# VREG_RT9166-28PVL_with_EN.net
KiCad netlist of a schematic drawn in Altium Designer
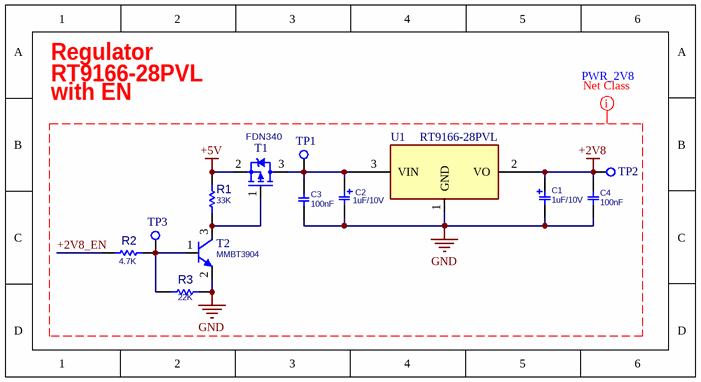
[diagram p0: VREG RT9166-28PVL with EN.SchDoc]

(export (version "E")
  (design (tool "Eeschema 10.0.6"))
  (components
    (comp (ref "C1")
      (value "1uF/10V")
      (footprint "C_TN_3216")
      (description "CAP, SMD, TAN")
      (libsource (lib "Passive") (part "CAP_SMD_TAN"))
    )
    (comp (ref "C2")
      (value "1uF/10V")
      (footprint "C_TN_3216")
      (description "CAP, SMD, TAN")
      (libsource (lib "Passive") (part "CAP_SMD_TAN"))
    )
    (comp (ref "C3")
      (value "100nF")
      (footprint "C0603S")
      (description "CAP, SMD, MLCC")
      (fields (field (name "MANF_P#") "MANF_PART#") (field (name "MANF") "Murata"))
      (libsource (lib "Passive") (part "CAP_SMD_MLCC"))
    )
    (comp (ref "C4")
      (value "100nF")
      (footprint "C0603S")
      (description "CAP, SMD, MLCC")
      (fields (field (name "MANF_P#") "MANF_PART#") (field (name "MANF") "Murata"))
      (libsource (lib "Passive") (part "CAP_SMD_MLCC"))
    )
    (comp (ref "R1")
      (value "33K")
      (footprint "R0603S")
      (description "RES, SMD")
      (fields (field (name "MANF_P#") "RK73H1ETTP4701F") (field (name "MANF") "KOA SPEER"))
      (libsource (lib "Passive") (part "RES_SMD"))
    )
    (comp (ref "R2")
      (value "4.7K")
      (footprint "R0603S")
      (description "RES, SMD")
      (fields (field (name "MANF_P#") "RK73H1ETTP4701F") (field (name "MANF") "KOA SPEER"))
      (libsource (lib "Passive") (part "RES_SMD"))
    )
    (comp (ref "R3")
      (value "22K")
      (footprint "R0603S")
      (description "RES, SMD")
      (fields (field (name "MANF_P#") "RK73H1ETTP4701F") (field (name "MANF") "KOA SPEER"))
      (libsource (lib "Passive") (part "RES_SMD"))
    )
    (comp (ref "T1")
      (value "FDN340")
      (footprint "SOT23_3")
      (description "MOSFET SMD P-CH 20V 2A")
      (fields (field (name "MANF_P#") "FDN360"))
      (libsource (lib "Transistor FET") (part "MOSP_FDN340_SOT23"))
    )
    (comp (ref "T2")
      (value "MMBT3904")
      (footprint "SOT23_3")
      (description "BJT, NPN, 40V, 0.2A, SMD, SOT23")
      (fields (field (name "MANF") "Diodes, NXP, FAIRCHILD, ON"))
      (libsource (lib "Transistor BJT") (part "NPN_MMBT3904_SOT23"))
    )
    (comp (ref "TP1")
      (value "Test Point")
      (footprint "TPSMD_C1")
      (libsource (lib "Passives") (part "Test Point"))
    )
    (comp (ref "TP2")
      (value "Test Point")
      (footprint "TPSMD_C1")
      (libsource (lib "Passives") (part "Test Point"))
    )
    (comp (ref "TP3")
      (value "Test Point")
      (footprint "TPSMD_C1")
      (libsource (lib "Passives") (part "Test Point"))
    )
    (comp (ref "U1")
      (value "RT9166-28PVL")
      (footprint "SOT23_3")
      (description "REG, Linear, Fixed, 2.8v, 0.3A/0.6A, SOT23")
      (fields (field (name "MANF") "TI"))
      (libsource (lib "PW Components 97_481") (part "VREG_RT9166A-28PVL_SOT23"))
    )
  )
  (nets
    (net (code "1") (name "+2V8") (class "Default")
      (node (ref "C1") (pin "1") (pinfunction "1_1") (pintype "passive"))
      (node (ref "C4") (pin "1") (pinfunction "1_1") (pintype "passive"))
      (node (ref "TP2") (pin "1") (pinfunction "TP_1") (pintype "passive"))
      (node (ref "U1") (pin "2") (pinfunction "VO_2") (pintype "passive"))
    )
    (net (code "2") (name "+5V") (class "Default")
      (node (ref "R1") (pin "2") (pinfunction "2_2") (pintype "passive"))
      (node (ref "T1") (pin "2") (pinfunction "S_2") (pintype "passive"))
    )
    (net (code "3") (name "/+2V8_EN") (class "Default")
      (node (ref "R2") (pin "2") (pinfunction "2_2") (pintype "passive"))
    )
    (net (code "4") (name "GND") (class "Default")
      (node (ref "C1") (pin "2") (pinfunction "2_2") (pintype "passive"))
      (node (ref "C2") (pin "2") (pinfunction "2_2") (pintype "passive"))
      (node (ref "C3") (pin "2") (pinfunction "2_2") (pintype "passive"))
      (node (ref "C4") (pin "2") (pinfunction "2_2") (pintype "passive"))
      (node (ref "R3") (pin "1") (pinfunction "1_1") (pintype "passive"))
      (node (ref "T2") (pin "2") (pinfunction "E_2") (pintype "passive"))
      (node (ref "U1") (pin "1") (pinfunction "GND_1") (pintype "passive"))
    )
    (net (code "5") (name "Net-(T1-D)") (class "Default")
      (node (ref "C2") (pin "1") (pinfunction "1_1") (pintype "passive"))
      (node (ref "C3") (pin "1") (pinfunction "1_1") (pintype "passive"))
      (node (ref "T1") (pin "3") (pinfunction "D_3") (pintype "passive"))
      (node (ref "TP1") (pin "1") (pinfunction "TP_1") (pintype "passive"))
      (node (ref "U1") (pin "3") (pinfunction "VIN_3") (pintype "passive"))
    )
    (net (code "6") (name "Net-(T1-G)") (class "Default")
      (node (ref "R1") (pin "1") (pinfunction "1_1") (pintype "passive"))
      (node (ref "T1") (pin "1") (pinfunction "G_1") (pintype "passive"))
      (node (ref "T2") (pin "3") (pinfunction "C_3") (pintype "passive"))
    )
    (net (code "7") (name "Net-(T2-B)") (class "Default")
      (node (ref "R2") (pin "1") (pinfunction "1_1") (pintype "passive"))
      (node (ref "R3") (pin "2") (pinfunction "2_2") (pintype "passive"))
      (node (ref "T2") (pin "1") (pinfunction "B_1") (pintype "passive"))
      (node (ref "TP3") (pin "1") (pinfunction "TP_1") (pintype "passive"))
    )
  )
)
